# Switch_Network.net
KiCad netlist of a schematic drawn in Altium Designer
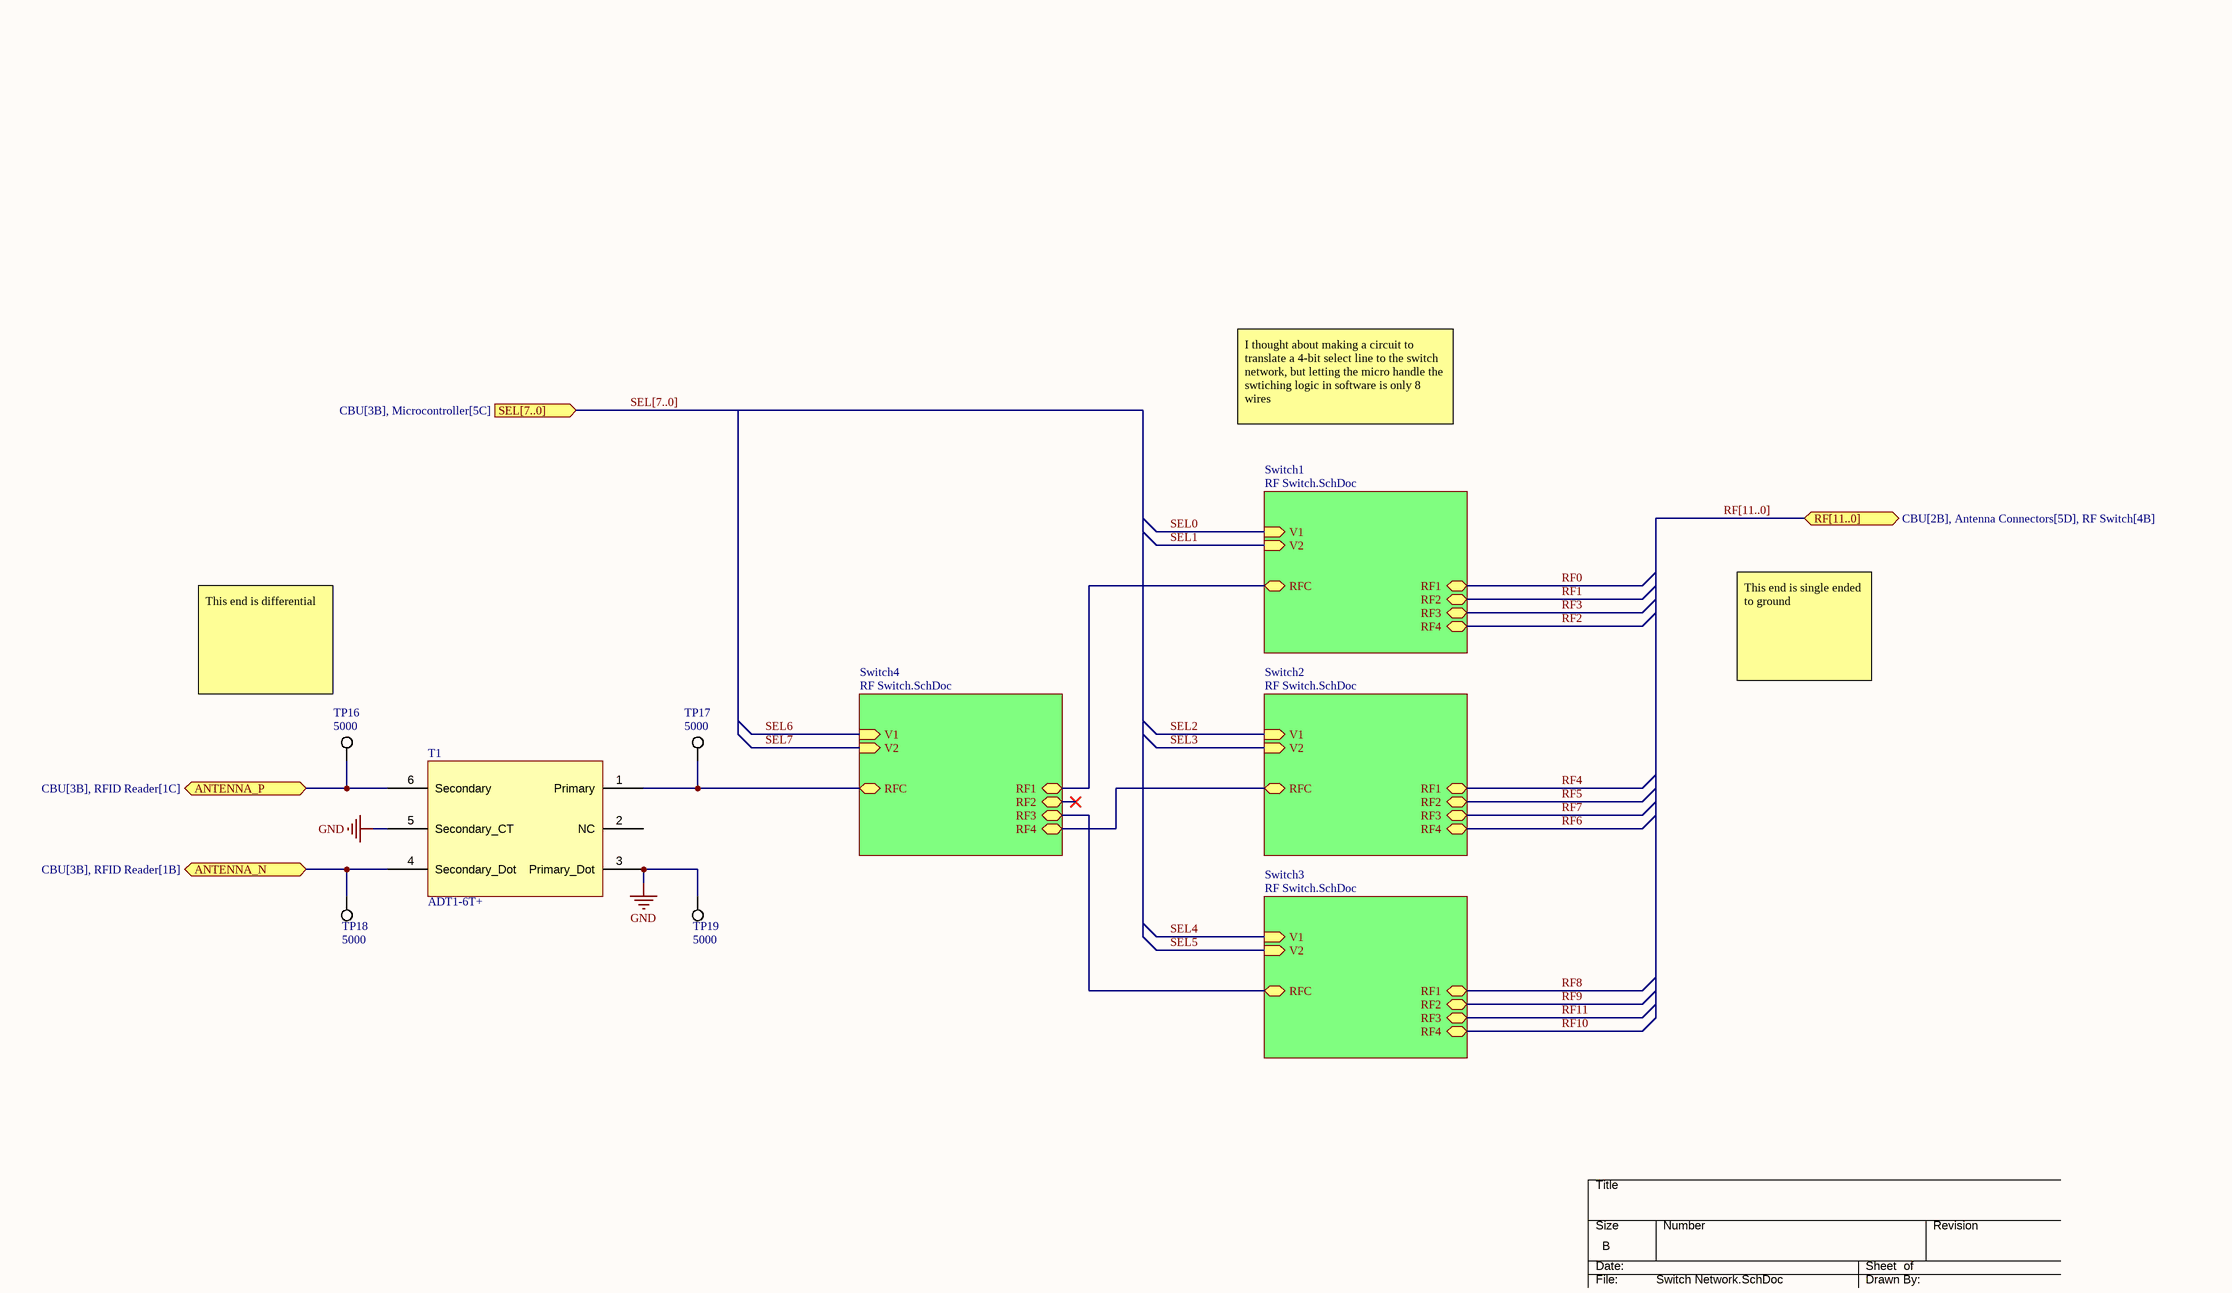
[diagram p0: Switch Network.SchDoc]

(export (version "E")
  (design (tool "Eeschema 10.0.6"))
  (components
    (comp (ref "T1")
      (value "ADT1-6T+")
      (footprint "ADT1-6T+")
      (description "RF Balun 30kHz ~ 125MHz 50 / 50Ohm 6-SMD, Flat Leads")
      (libsource (lib "CBU-PCB") (part "ADT1-6T+"))
    )
    (comp (ref "TP16")
      (value "5000")
      (footprint "FP-5000-MFG")
      (description "Red PC Test Point, Miniature Phosphor Bronze Silver Plating Through Hole Mounting Type")
      (libsource (lib "CBU-PCB") (part "5000"))
    )
    (comp (ref "TP17")
      (value "5000")
      (footprint "FP-5000-MFG")
      (description "Red PC Test Point, Miniature Phosphor Bronze Silver Plating Through Hole Mounting Type")
      (libsource (lib "CBU-PCB") (part "5000"))
    )
    (comp (ref "TP18")
      (value "5000")
      (footprint "FP-5000-MFG")
      (description "Red PC Test Point, Miniature Phosphor Bronze Silver Plating Through Hole Mounting Type")
      (libsource (lib "CBU-PCB") (part "5000"))
    )
    (comp (ref "TP19")
      (value "5000")
      (footprint "FP-5000-MFG")
      (description "Red PC Test Point, Miniature Phosphor Bronze Silver Plating Through Hole Mounting Type")
      (libsource (lib "CBU-PCB") (part "5000"))
    )
  )
  (nets
    (net (code "1") (name "/ANTENNA_N") (class "Default")
      (node (ref "T1") (pin "4") (pinfunction "Secondary_Dot_4") (pintype "passive"))
      (node (ref "TP18") (pin "1") (pinfunction "1_1") (pintype "passive"))
    )
    (net (code "2") (name "/ANTENNA_P") (class "Default")
      (node (ref "T1") (pin "6") (pinfunction "Secondary_6") (pintype "passive"))
      (node (ref "TP16") (pin "1") (pinfunction "1_1") (pintype "passive"))
    )
    (net (code "19") (name "/RFC") (class "Default")
      (node (ref "T1") (pin "1") (pinfunction "Primary_1") (pintype "passive"))
      (node (ref "TP17") (pin "1") (pinfunction "1_1") (pintype "passive"))
    )
    (net (code "30") (name "GND") (class "Default")
      (node (ref "T1") (pin "3") (pinfunction "Primary_Dot_3") (pintype "passive"))
      (node (ref "T1") (pin "5") (pinfunction "Secondary_CT_5") (pintype "passive"))
      (node (ref "TP19") (pin "1") (pinfunction "1_1") (pintype "passive"))
    )
    (net (code "31") (name "unconnected-(T1-NC-Pad2)") (class "Default")
      (node (ref "T1") (pin "2") (pinfunction "NC_2") (pintype "passive"))
    )
  )
)
